# mother_card_03.net
KiCad netlist of a schematic drawn in EAGLE
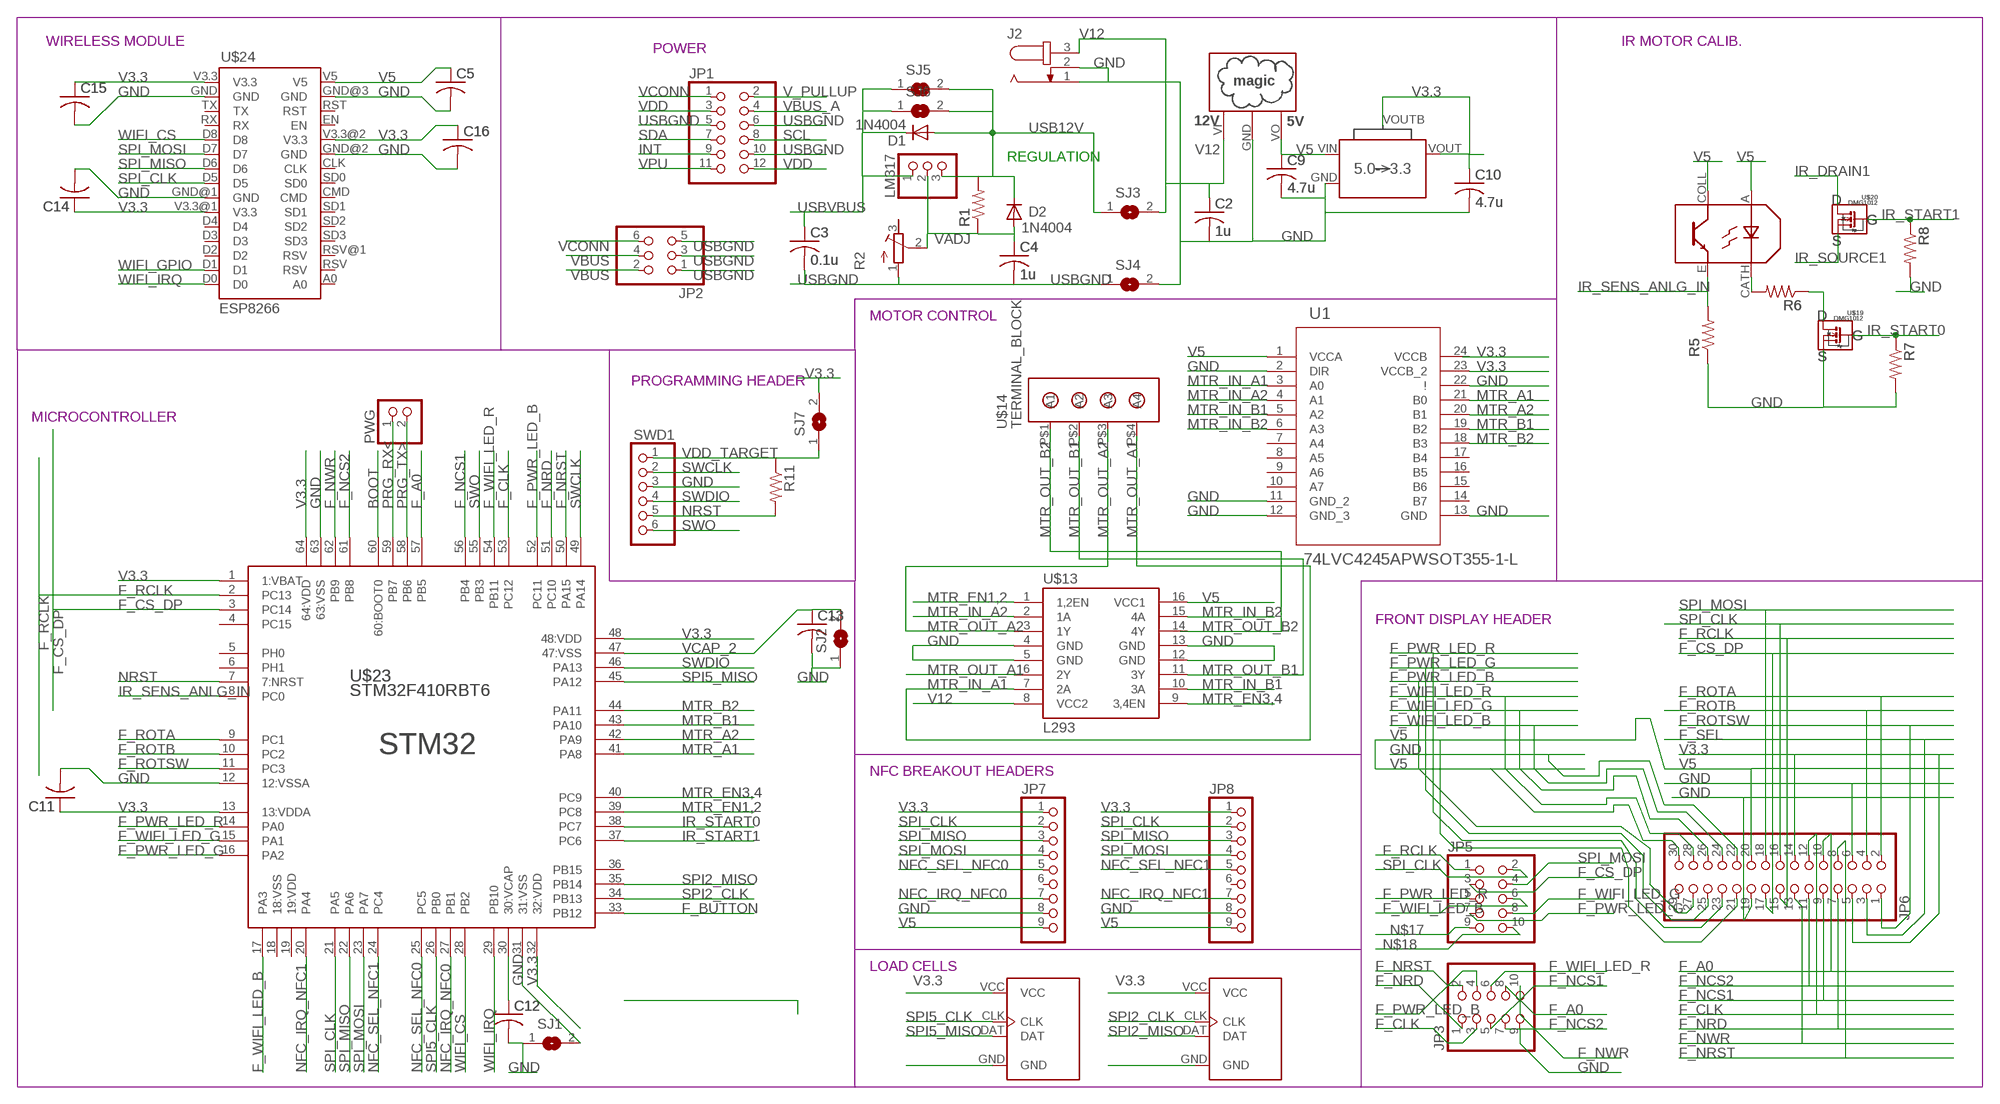
[diagram p0: schematic, sheet 1]

(export (version "E")
  (design (tool "Eeschema 10.0.6"))
  (components
    (comp (ref "C2")
      (value "1u")
      (footprint "eagle-import:C0805")
      (libsource (lib "eagle-import") (part "C-USC0805"))
    )
    (comp (ref "C3")
      (value "0.1u")
      (footprint "eagle-import:C0805")
      (libsource (lib "eagle-import") (part "C-USC0805"))
    )
    (comp (ref "C4")
      (value "1u")
      (footprint "eagle-import:C0805")
      (libsource (lib "eagle-import") (part "C-USC0805"))
    )
    (comp (ref "C5")
      (value "C-USC0805")
      (footprint "eagle-import:C0805")
      (libsource (lib "eagle-import") (part "C-USC0805"))
    )
    (comp (ref "C9")
      (value "4.7u")
      (footprint "eagle-import:C0805")
      (libsource (lib "eagle-import") (part "C-USC0805"))
    )
    (comp (ref "C10")
      (value "4.7u")
      (footprint "eagle-import:C0805")
      (libsource (lib "eagle-import") (part "C-USC0805"))
    )
    (comp (ref "C11")
      (value "C-USC0805")
      (footprint "eagle-import:C0805")
      (libsource (lib "eagle-import") (part "C-USC0805"))
    )
    (comp (ref "C12")
      (value "C-USC0805")
      (footprint "eagle-import:C0805")
      (libsource (lib "eagle-import") (part "C-USC0805"))
    )
    (comp (ref "C13")
      (value "C-USC0805")
      (footprint "eagle-import:C0805")
      (libsource (lib "eagle-import") (part "C-USC0805"))
    )
    (comp (ref "C14")
      (value "C-USC0805")
      (footprint "eagle-import:C0805")
      (libsource (lib "eagle-import") (part "C-USC0805"))
    )
    (comp (ref "C15")
      (value "C-USC0805")
      (footprint "eagle-import:C0805")
      (libsource (lib "eagle-import") (part "C-USC0805"))
    )
    (comp (ref "C16")
      (value "C-USC0805")
      (footprint "eagle-import:C0805")
      (libsource (lib "eagle-import") (part "C-USC0805"))
    )
    (comp (ref "D1")
      (value "1N4004")
      (footprint "eagle-import:DO41-10")
      (libsource (lib "eagle-import") (part "1N4004"))
    )
    (comp (ref "D2")
      (value "1N4004")
      (footprint "eagle-import:DO41-10")
      (libsource (lib "eagle-import") (part "1N4004"))
    )
    (comp (ref "J2")
      (value "JACK-PLUG0")
      (footprint "eagle-import:SPC4077")
      (libsource (lib "eagle-import") (part "JACK-PLUG0"))
    )
    (comp (ref "JP1")
      (value "PINHD-2X6")
      (footprint "eagle-import:2X06")
      (libsource (lib "eagle-import") (part "PINHD-2X6"))
    )
    (comp (ref "JP2")
      (value "PINHD-2X3")
      (footprint "eagle-import:2X03")
      (libsource (lib "eagle-import") (part "PINHD-2X3"))
    )
    (comp (ref "JP3")
      (value "PINHD-2X5")
      (footprint "eagle-import:2X05")
      (libsource (lib "eagle-import") (part "PINHD-2X5"))
    )
    (comp (ref "JP5")
      (value "PINHD-2X5")
      (footprint "eagle-import:2X05")
      (libsource (lib "eagle-import") (part "PINHD-2X5"))
    )
    (comp (ref "JP6")
      (value "PINHD-2X15/SOCK")
      (footprint "eagle-import:2X15_SOCK")
      (libsource (lib "eagle-import") (part "PINHD-2X15/SOCK"))
    )
    (comp (ref "JP7")
      (value "PINHD-1X9/90")
      (footprint "eagle-import:1X09_90")
      (libsource (lib "eagle-import") (part "PINHD-1X9/90"))
    )
    (comp (ref "JP8")
      (value "PINHD-1X9/90")
      (footprint "eagle-import:1X09_90")
      (libsource (lib "eagle-import") (part "PINHD-1X9/90"))
    )
    (comp (ref "LM317")
      (value "PINHD-1X3")
      (footprint "eagle-import:1X03")
      (libsource (lib "eagle-import") (part "PINHD-1X3"))
    )
    (comp (ref "PWG")
      (value "PINHD-1X2")
      (footprint "eagle-import:1X02")
      (libsource (lib "eagle-import") (part "PINHD-1X2"))
    )
    (comp (ref "R1")
      (value "R-US_R0805")
      (footprint "eagle-import:R0805")
      (libsource (lib "eagle-import") (part "seniorDesign_R-US_R0805"))
    )
    (comp (ref "R2")
      (value "R-TRIMM64W")
      (footprint "eagle-import:RTRIM64W")
      (libsource (lib "eagle-import") (part "R-TRIMM64W"))
    )
    (comp (ref "R5")
      (value "R-US_R0805")
      (footprint "eagle-import:R0805")
      (libsource (lib "eagle-import") (part "seniorDesign_R-US_R0805"))
    )
    (comp (ref "R6")
      (value "R-US_R0805")
      (footprint "eagle-import:R0805")
      (libsource (lib "eagle-import") (part "seniorDesign_R-US_R0805"))
    )
    (comp (ref "R7")
      (value "R-US_R0805")
      (footprint "eagle-import:R0805")
      (libsource (lib "eagle-import") (part "seniorDesign_R-US_R0805"))
    )
    (comp (ref "R8")
      (value "R-US_R0805")
      (footprint "eagle-import:R0805")
      (libsource (lib "eagle-import") (part "seniorDesign_R-US_R0805"))
    )
    (comp (ref "R11")
      (value "R-US_R0805")
      (footprint "eagle-import:R0805")
      (libsource (lib "eagle-import") (part "R-US_R0805"))
    )
    (comp (ref "SJ1") (value "SJ") (footprint "eagle-import:SJ") (libsource (lib "eagle-import") (part "SJ")))
    (comp (ref "SJ2") (value "SJ") (footprint "eagle-import:SJ") (libsource (lib "eagle-import") (part "SJ")))
    (comp (ref "SJ3") (value "SJ") (footprint "eagle-import:SJ") (libsource (lib "eagle-import") (part "SJ")))
    (comp (ref "SJ4") (value "SJ") (footprint "eagle-import:SJ") (libsource (lib "eagle-import") (part "SJ")))
    (comp (ref "SJ5") (value "SJ") (footprint "eagle-import:SJ") (libsource (lib "eagle-import") (part "SJ")))
    (comp (ref "SJ6") (value "SJ") (footprint "eagle-import:SJ") (libsource (lib "eagle-import") (part "SJ")))
    (comp (ref "SJ7") (value "SJ") (footprint "eagle-import:SJ") (libsource (lib "eagle-import") (part "SJ")))
    (comp (ref "SWD1")
      (value "PINHD-1X6")
      (footprint "eagle-import:1X06")
      (libsource (lib "eagle-import") (part "PINHD-1X6"))
    )
    (comp (ref "U$13")
      (value "L293")
      (footprint "eagle-import:DIL16")
      (libsource (lib "eagle-import") (part "L293"))
    )
    (comp (ref "U$14")
      (value "TERMINAL_BLOCK")
      (footprint "eagle-import:1X4_BLOCK")
      (libsource (lib "eagle-import") (part "TERMINAL_BLOCK"))
    )
    (comp (ref "U$15")
      (value "AP2114H")
      (footprint "eagle-import:AP2114H")
      (libsource (lib "eagle-import") (part "AP2114H"))
    )
    (comp (ref "U$16")
      (value "OKI-78SR-W36")
      (footprint "eagle-import:SIP3")
      (libsource (lib "eagle-import") (part "OKI-78SR-W36"))
    )
    (comp (ref "U$18")
      (value "TCRT5000")
      (footprint "eagle-import:TCRT5000")
      (libsource (lib "eagle-import") (part "TCRT5000"))
    )
    (comp (ref "U$19")
      (value "DMG1012")
      (footprint "eagle-import:SOT323")
      (libsource (lib "eagle-import") (part "DMG1012"))
    )
    (comp (ref "U$20")
      (value "DMG1012")
      (footprint "eagle-import:SOT323")
      (libsource (lib "eagle-import") (part "DMG1012"))
    )
    (comp (ref "U$21")
      (value "HX711")
      (footprint "eagle-import:HX711")
      (libsource (lib "eagle-import") (part "HX711"))
    )
    (comp (ref "U$22")
      (value "HX711")
      (footprint "eagle-import:HX711")
      (libsource (lib "eagle-import") (part "HX711"))
    )
    (comp (ref "U$23")
      (value "STM32F410RBT6")
      (footprint "eagle-import:QFP50P1200X1200X160-64N")
      (libsource (lib "eagle-import") (part "STM32F410RBT6"))
    )
    (comp (ref "U$24")
      (value "ESP8266")
      (footprint "eagle-import:ESP8266")
      (libsource (lib "eagle-import") (part "ESP8266"))
    )
    (comp (ref "U1")
      (value "74LVC4245APWSOT355-1-L")
      (footprint "eagle-import:SOT355-1-L")
      (fields (field (name "MANUFACTURER_PART_NUMBER") "74LVC4245APW"))
      (libsource (lib "eagle-import") (part "74LVC4245APWSOT355-1-L"))
    )
  )
  (nets
    (net (code "1") (name "/BOOT") (class "Default")
      (node (ref "U$23") (pin "60") (pinfunction "60:BOOT0_60") (pintype "bidirectional"))
    )
    (net (code "2") (name "/F_A0") (class "Default")
      (node (ref "JP3") (pin "8") (pinfunction "8_8") (pintype "passive"))
      (node (ref "JP6") (pin "10") (pinfunction "10_10") (pintype "passive"))
      (node (ref "U$23") (pin "57") (pinfunction "PB5_57") (pintype "bidirectional"))
    )
    (net (code "3") (name "/F_BUTTON") (class "Default")
      (node (ref "U$23") (pin "33") (pinfunction "PB12_33") (pintype "bidirectional"))
    )
    (net (code "4") (name "/F_CLK") (class "Default")
      (node (ref "JP3") (pin "3") (pinfunction "3_3") (pintype "passive"))
      (node (ref "JP6") (pin "12") (pinfunction "12_12") (pintype "passive"))
      (node (ref "U$23") (pin "53") (pinfunction "PC12_53") (pintype "bidirectional"))
    )
    (net (code "5") (name "/F_CS_DP") (class "Default")
      (node (ref "JP5") (pin "3") (pinfunction "3_3") (pintype "passive"))
      (node (ref "JP6") (pin "17") (pinfunction "17_17") (pintype "passive"))
      (node (ref "U$23") (pin "3") (pinfunction "PC14_3") (pintype "bidirectional"))
    )
    (net (code "6") (name "/F_NCS1") (class "Default")
      (node (ref "JP3") (pin "5") (pinfunction "5_5") (pintype "passive"))
      (node (ref "JP6") (pin "9") (pinfunction "9_9") (pintype "passive"))
      (node (ref "U$23") (pin "56") (pinfunction "PB4_56") (pintype "bidirectional"))
    )
    (net (code "7") (name "/F_NCS2") (class "Default")
      (node (ref "JP3") (pin "7") (pinfunction "7_7") (pintype "passive"))
      (node (ref "JP6") (pin "11") (pinfunction "11_11") (pintype "passive"))
      (node (ref "U$23") (pin "61") (pinfunction "PB8_61") (pintype "bidirectional"))
    )
    (net (code "8") (name "/F_NRD") (class "Default")
      (node (ref "JP3") (pin "1") (pinfunction "1_1") (pintype "passive"))
      (node (ref "JP6") (pin "7") (pinfunction "7_7") (pintype "passive"))
      (node (ref "U$23") (pin "51") (pinfunction "PC10_51") (pintype "bidirectional"))
    )
    (net (code "9") (name "/F_NRST") (class "Default")
      (node (ref "JP3") (pin "2") (pinfunction "2_2") (pintype "passive"))
      (node (ref "JP6") (pin "8") (pinfunction "8_8") (pintype "passive"))
      (node (ref "U$23") (pin "50") (pinfunction "PA15_50") (pintype "bidirectional"))
    )
    (net (code "10") (name "/F_NWR") (class "Default")
      (node (ref "JP3") (pin "10") (pinfunction "10_10") (pintype "passive"))
      (node (ref "JP6") (pin "13") (pinfunction "13_13") (pintype "passive"))
      (node (ref "U$23") (pin "62") (pinfunction "PB9_62") (pintype "bidirectional"))
    )
    (net (code "11") (name "/F_PWR_LED_B") (class "Default")
      (node (ref "JP3") (pin "4") (pinfunction "4_4") (pintype "passive"))
      (node (ref "JP6") (pin "27") (pinfunction "27_27") (pintype "passive"))
      (node (ref "U$23") (pin "52") (pinfunction "PC11_52") (pintype "bidirectional"))
    )
    (net (code "12") (name "/F_PWR_LED_G") (class "Default")
      (node (ref "JP5") (pin "7") (pinfunction "7_7") (pintype "passive"))
      (node (ref "JP6") (pin "25") (pinfunction "25_25") (pintype "passive"))
      (node (ref "U$23") (pin "16") (pinfunction "PA2_16") (pintype "bidirectional"))
    )
    (net (code "13") (name "/F_PWR_LED_R") (class "Default")
      (node (ref "JP5") (pin "5") (pinfunction "5_5") (pintype "passive"))
      (node (ref "JP6") (pin "23") (pinfunction "23_23") (pintype "passive"))
      (node (ref "U$23") (pin "14") (pinfunction "PA0_14") (pintype "bidirectional"))
    )
    (net (code "14") (name "/F_RCLK") (class "Default")
      (node (ref "JP5") (pin "1") (pinfunction "1_1") (pintype "passive"))
      (node (ref "JP6") (pin "15") (pinfunction "15_15") (pintype "passive"))
      (node (ref "U$23") (pin "2") (pinfunction "PC13_2") (pintype "bidirectional"))
    )
    (net (code "15") (name "/F_ROTA") (class "Default")
      (node (ref "JP6") (pin "2") (pinfunction "2_2") (pintype "passive"))
      (node (ref "U$23") (pin "9") (pinfunction "PC1_9") (pintype "bidirectional"))
    )
    (net (code "16") (name "/F_ROTB") (class "Default")
      (node (ref "JP6") (pin "4") (pinfunction "4_4") (pintype "passive"))
      (node (ref "U$23") (pin "10") (pinfunction "PC2_10") (pintype "bidirectional"))
    )
    (net (code "17") (name "/F_ROTSW") (class "Default")
      (node (ref "JP6") (pin "1") (pinfunction "1_1") (pintype "passive"))
      (node (ref "U$23") (pin "11") (pinfunction "PC3_11") (pintype "bidirectional"))
    )
    (net (code "18") (name "/F_SEL") (class "Default")
      (node (ref "JP6") (pin "3") (pinfunction "3_3") (pintype "passive"))
    )
    (net (code "19") (name "/F_WIFI_LED_B") (class "Default")
      (node (ref "JP5") (pin "6") (pinfunction "6_6") (pintype "passive"))
      (node (ref "JP6") (pin "24") (pinfunction "24_24") (pintype "passive"))
      (node (ref "U$23") (pin "17") (pinfunction "PA3_17") (pintype "bidirectional"))
    )
    (net (code "20") (name "/F_WIFI_LED_G") (class "Default")
      (node (ref "JP5") (pin "8") (pinfunction "8_8") (pintype "passive"))
      (node (ref "JP6") (pin "26") (pinfunction "26_26") (pintype "passive"))
      (node (ref "U$23") (pin "15") (pinfunction "PA1_15") (pintype "bidirectional"))
    )
    (net (code "21") (name "/F_WIFI_LED_R") (class "Default")
      (node (ref "JP3") (pin "6") (pinfunction "6_6") (pintype "passive"))
      (node (ref "JP6") (pin "28") (pinfunction "28_28") (pintype "passive"))
      (node (ref "U$23") (pin "54") (pinfunction "PB11_54") (pintype "bidirectional"))
    )
    (net (code "22") (name "/GND") (class "Default")
      (node (ref "C10") (pin "2") (pinfunction "2_2") (pintype "passive"))
      (node (ref "C11") (pin "2") (pinfunction "2_2") (pintype "passive"))
      (node (ref "C12") (pin "2") (pinfunction "2_2") (pintype "passive"))
      (node (ref "C13") (pin "2") (pinfunction "2_2") (pintype "passive"))
      (node (ref "C14") (pin "2") (pinfunction "2_2") (pintype "passive"))
      (node (ref "C15") (pin "2") (pinfunction "2_2") (pintype "passive"))
      (node (ref "C16") (pin "2") (pinfunction "2_2") (pintype "passive"))
      (node (ref "C2") (pin "2") (pinfunction "2_2") (pintype "passive"))
      (node (ref "C5") (pin "2") (pinfunction "2_2") (pintype "passive"))
      (node (ref "C9") (pin "2") (pinfunction "2_2") (pintype "passive"))
      (node (ref "J2") (pin "1") (pinfunction "1_1") (pintype "passive"))
      (node (ref "J2") (pin "2") (pinfunction "2_2") (pintype "passive"))
      (node (ref "JP3") (pin "9") (pinfunction "9_9") (pintype "passive"))
      (node (ref "JP6") (pin "19") (pinfunction "19_19") (pintype "passive"))
      (node (ref "JP6") (pin "22") (pinfunction "22_22") (pintype "passive"))
      (node (ref "JP6") (pin "6") (pinfunction "6_6") (pintype "passive"))
      (node (ref "JP7") (pin "8") (pinfunction "8_8") (pintype "passive"))
      (node (ref "JP8") (pin "8") (pinfunction "8_8") (pintype "passive"))
      (node (ref "R5") (pin "1") (pinfunction "1_1") (pintype "passive"))
      (node (ref "R7") (pin "2") (pinfunction "2_2") (pintype "passive"))
      (node (ref "R8") (pin "2") (pinfunction "2_2") (pintype "passive"))
      (node (ref "SJ1") (pin "1") (pinfunction "1_1") (pintype "passive"))
      (node (ref "SJ1") (pin "2") (pinfunction "2_2") (pintype "passive"))
      (node (ref "SJ2") (pin "1") (pinfunction "1_1") (pintype "passive"))
      (node (ref "SJ4") (pin "2") (pinfunction "2_2") (pintype "passive"))
      (node (ref "SWD1") (pin "3") (pinfunction "3_3") (pintype "passive"))
      (node (ref "U$13") (pin "12") (pinfunction "GND_12") (pintype "bidirectional"))
      (node (ref "U$13") (pin "13") (pinfunction "GND_13") (pintype "bidirectional"))
      (node (ref "U$13") (pin "4") (pinfunction "GND_4") (pintype "bidirectional"))
      (node (ref "U$13") (pin "5") (pinfunction "GND_5") (pintype "bidirectional"))
      (node (ref "U$15") (pin "GND") (pinfunction "GND_GND") (pintype "power_in"))
      (node (ref "U$16") (pin "GND") (pinfunction "P$2_GND") (pintype "power_in"))
      (node (ref "U$19") (pin "S") (pinfunction "S_S") (pintype "bidirectional"))
      (node (ref "U$21") (pin "GND") (pinfunction "GND_GND") (pintype "power_in"))
      (node (ref "U$22") (pin "GND") (pinfunction "GND_GND") (pintype "power_in"))
      (node (ref "U$23") (pin "12") (pinfunction "12:VSSA_12") (pintype "bidirectional"))
      (node (ref "U$23") (pin "31") (pinfunction "31:VSS_31") (pintype "bidirectional"))
      (node (ref "U$23") (pin "63") (pinfunction "63:VSS_63") (pintype "bidirectional"))
      (node (ref "U$24") (pin "GND") (pinfunction "GND_GND") (pintype "bidirectional"))
      (node (ref "U$24") (pin "GND@1") (pinfunction "GND_GND@1") (pintype "bidirectional"))
      (node (ref "U$24") (pin "GND@2") (pinfunction "GND_GND@2") (pintype "bidirectional"))
      (node (ref "U$24") (pin "GND@3") (pinfunction "GND_GND@3") (pintype "bidirectional"))
      (node (ref "U1") (pin "11") (pinfunction "GND_2_11") (pintype "power_in"))
      (node (ref "U1") (pin "12") (pinfunction "GND_3_12") (pintype "power_in"))
      (node (ref "U1") (pin "13") (pinfunction "GND_13") (pintype "power_in"))
      (node (ref "U1") (pin "2") (pinfunction "DIR_2") (pintype "input"))
      (node (ref "U1") (pin "22") (pinfunction "~_22") (pintype "input"))
    )
    (net (code "23") (name "/INT") (class "Default")
      (node (ref "JP1") (pin "9") (pinfunction "9_9") (pintype "passive"))
    )
    (net (code "24") (name "/IR_DRAIN1") (class "Default")
      (node (ref "U$20") (pin "D") (pinfunction "D_D") (pintype "bidirectional"))
    )
    (net (code "25") (name "/IR_SENS_ANLG_IN") (class "Default")
      (node (ref "R5") (pin "2") (pinfunction "2_2") (pintype "passive"))
      (node (ref "U$18") (pin "E") (pinfunction "E_E") (pintype "bidirectional"))
      (node (ref "U$23") (pin "8") (pinfunction "PC0_8") (pintype "bidirectional"))
    )
    (net (code "26") (name "/IR_SOURCE1") (class "Default")
      (node (ref "U$20") (pin "S") (pinfunction "S_S") (pintype "bidirectional"))
    )
    (net (code "27") (name "/IR_START0") (class "Default")
      (node (ref "R7") (pin "1") (pinfunction "1_1") (pintype "passive"))
      (node (ref "U$19") (pin "G") (pinfunction "G_G") (pintype "bidirectional"))
      (node (ref "U$23") (pin "38") (pinfunction "PC7_38") (pintype "bidirectional"))
    )
    (net (code "28") (name "/IR_START1") (class "Default")
      (node (ref "R8") (pin "1") (pinfunction "1_1") (pintype "passive"))
      (node (ref "U$20") (pin "G") (pinfunction "G_G") (pintype "bidirectional"))
      (node (ref "U$23") (pin "37") (pinfunction "PC6_37") (pintype "bidirectional"))
    )
    (net (code "29") (name "/MTR_A1") (class "Default")
      (node (ref "U$23") (pin "41") (pinfunction "PA8_41") (pintype "bidirectional"))
      (node (ref "U1") (pin "21") (pinfunction "B0_21") (pintype "bidirectional"))
    )
    (net (code "30") (name "/MTR_A2") (class "Default")
      (node (ref "U$23") (pin "42") (pinfunction "PA9_42") (pintype "bidirectional"))
      (node (ref "U1") (pin "20") (pinfunction "B1_20") (pintype "bidirectional"))
    )
    (net (code "31") (name "/MTR_B1") (class "Default")
      (node (ref "U$23") (pin "43") (pinfunction "PA10_43") (pintype "bidirectional"))
      (node (ref "U1") (pin "19") (pinfunction "B2_19") (pintype "bidirectional"))
    )
    (net (code "32") (name "/MTR_B2") (class "Default")
      (node (ref "U$23") (pin "44") (pinfunction "PA11_44") (pintype "bidirectional"))
      (node (ref "U1") (pin "18") (pinfunction "B3_18") (pintype "bidirectional"))
    )
    (net (code "33") (name "/MTR_EN1,2") (class "Default")
      (node (ref "U$13") (pin "1") (pinfunction "1,2EN_1") (pintype "bidirectional"))
      (node (ref "U$23") (pin "39") (pinfunction "PC8_39") (pintype "bidirectional"))
    )
    (net (code "34") (name "/MTR_EN3,4") (class "Default")
      (node (ref "U$13") (pin "9") (pinfunction "3,4EN_9") (pintype "bidirectional"))
      (node (ref "U$23") (pin "40") (pinfunction "PC9_40") (pintype "bidirectional"))
    )
    (net (code "35") (name "/MTR_IN_A1") (class "Default")
      (node (ref "U$13") (pin "7") (pinfunction "2A_7") (pintype "bidirectional"))
      (node (ref "U$14") (pin "P$4") (pinfunction "A4_P$4") (pintype "bidirectional"))
      (node (ref "U1") (pin "3") (pinfunction "A0_3") (pintype "bidirectional"))
    )
    (net (code "36") (name "/MTR_IN_A2") (class "Default")
      (node (ref "U$13") (pin "2") (pinfunction "1A_2") (pintype "bidirectional"))
      (node (ref "U1") (pin "4") (pinfunction "A1_4") (pintype "bidirectional"))
    )
    (net (code "37") (name "/MTR_IN_B1") (class "Default")
      (node (ref "U$13") (pin "10") (pinfunction "3A_10") (pintype "bidirectional"))
      (node (ref "U1") (pin "5") (pinfunction "A2_5") (pintype "bidirectional"))
    )
    (net (code "38") (name "/MTR_IN_B2") (class "Default")
      (node (ref "U$13") (pin "15") (pinfunction "4A_15") (pintype "bidirectional"))
      (node (ref "U1") (pin "6") (pinfunction "A3_6") (pintype "bidirectional"))
    )
    (net (code "39") (name "/MTR_OUT_A1") (class "Default")
      (node (ref "U$13") (pin "6") (pinfunction "2Y_6") (pintype "bidirectional"))
    )
    (net (code "40") (name "/MTR_OUT_A2") (class "Default")
      (node (ref "U$13") (pin "3") (pinfunction "1Y_3") (pintype "bidirectional"))
      (node (ref "U$14") (pin "P$3") (pinfunction "A3_P$3") (pintype "bidirectional"))
    )
    (net (code "41") (name "/MTR_OUT_B1") (class "Default")
      (node (ref "U$13") (pin "11") (pinfunction "3Y_11") (pintype "bidirectional"))
      (node (ref "U$14") (pin "P$2") (pinfunction "A2_P$2") (pintype "bidirectional"))
    )
    (net (code "42") (name "/MTR_OUT_B2") (class "Default")
      (node (ref "U$13") (pin "14") (pinfunction "4Y_14") (pintype "bidirectional"))
      (node (ref "U$14") (pin "P$1") (pinfunction "A1_P$1") (pintype "bidirectional"))
    )
    (net (code "43") (name "/N$17") (class "Default")
      (node (ref "JP5") (pin "9") (pinfunction "9_9") (pintype "passive"))
    )
    (net (code "44") (name "/N$18") (class "Default")
      (node (ref "JP5") (pin "10") (pinfunction "10_10") (pintype "passive"))
    )
    (net (code "45") (name "/NFC_IRQ_NFC0") (class "Default")
      (node (ref "JP7") (pin "7") (pinfunction "7_7") (pintype "passive"))
      (node (ref "U$23") (pin "27") (pinfunction "PB1_27") (pintype "bidirectional"))
    )
    (net (code "46") (name "/NFC_IRQ_NFC1") (class "Default")
      (node (ref "JP8") (pin "7") (pinfunction "7_7") (pintype "passive"))
      (node (ref "U$23") (pin "20") (pinfunction "PA4_20") (pintype "bidirectional"))
    )
    (net (code "47") (name "/NFC_SEL_NFC0") (class "Default")
      (node (ref "JP7") (pin "5") (pinfunction "5_5") (pintype "passive"))
      (node (ref "U$23") (pin "25") (pinfunction "PC5_25") (pintype "bidirectional"))
    )
    (net (code "48") (name "/NFC_SEL_NFC1") (class "Default")
      (node (ref "JP8") (pin "5") (pinfunction "5_5") (pintype "passive"))
      (node (ref "U$23") (pin "24") (pinfunction "PC4_24") (pintype "bidirectional"))
    )
    (net (code "49") (name "/NRST") (class "Default")
      (node (ref "R11") (pin "2") (pinfunction "2_2") (pintype "passive"))
      (node (ref "SWD1") (pin "5") (pinfunction "5_5") (pintype "passive"))
      (node (ref "U$23") (pin "7") (pinfunction "7:NRST_7") (pintype "bidirectional"))
    )
    (net (code "50") (name "/PRG_RX<") (class "Default")
      (node (ref "PWG") (pin "1") (pinfunction "1_1") (pintype "passive"))
      (node (ref "U$23") (pin "59") (pinfunction "PB7_59") (pintype "bidirectional"))
    )
    (net (code "51") (name "/PRG_TX>") (class "Default")
      (node (ref "PWG") (pin "2") (pinfunction "2_2") (pintype "passive"))
      (node (ref "U$23") (pin "58") (pinfunction "PB6_58") (pintype "bidirectional"))
    )
    (net (code "52") (name "/SCL") (class "Default")
      (node (ref "JP1") (pin "8") (pinfunction "8_8") (pintype "passive"))
    )
    (net (code "53") (name "/SDA") (class "Default")
      (node (ref "JP1") (pin "7") (pinfunction "7_7") (pintype "passive"))
    )
    (net (code "54") (name "/SPI2_CLK") (class "Default")
      (node (ref "U$22") (pin "CLK") (pinfunction "CLK_CLK") (pintype "bidirectional"))
      (node (ref "U$23") (pin "34") (pinfunction "PB13_34") (pintype "bidirectional"))
    )
    (net (code "55") (name "/SPI2_MISO") (class "Default")
      (node (ref "U$22") (pin "DAT") (pinfunction "DAT_DAT") (pintype "bidirectional"))
      (node (ref "U$23") (pin "35") (pinfunction "PB14_35") (pintype "bidirectional"))
    )
    (net (code "56") (name "/SPI5_CLK") (class "Default")
      (node (ref "U$21") (pin "CLK") (pinfunction "CLK_CLK") (pintype "bidirectional"))
      (node (ref "U$23") (pin "26") (pinfunction "PB0_26") (pintype "bidirectional"))
    )
    (net (code "57") (name "/SPI5_MISO") (class "Default")
      (node (ref "U$21") (pin "DAT") (pinfunction "DAT_DAT") (pintype "bidirectional"))
      (node (ref "U$23") (pin "45") (pinfunction "PA12_45") (pintype "bidirectional"))
    )
    (net (code "58") (name "/SPI_CLK") (class "Default")
      (node (ref "JP5") (pin "2") (pinfunction "2_2") (pintype "passive"))
      (node (ref "JP6") (pin "16") (pinfunction "16_16") (pintype "passive"))
      (node (ref "JP7") (pin "2") (pinfunction "2_2") (pintype "passive"))
      (node (ref "JP8") (pin "2") (pinfunction "2_2") (pintype "passive"))
      (node (ref "U$23") (pin "21") (pinfunction "PA5_21") (pintype "bidirectional"))
      (node (ref "U$24") (pin "D5") (pinfunction "D5_D5") (pintype "bidirectional"))
    )
    (net (code "59") (name "/SPI_MISO") (class "Default")
      (node (ref "JP7") (pin "3") (pinfunction "3_3") (pintype "passive"))
      (node (ref "JP8") (pin "3") (pinfunction "3_3") (pintype "passive"))
      (node (ref "U$23") (pin "22") (pinfunction "PA6_22") (pintype "bidirectional"))
      (node (ref "U$24") (pin "D6") (pinfunction "D6_D6") (pintype "bidirectional"))
    )
    (net (code "60") (name "/SPI_MOSI") (class "Default")
      (node (ref "JP5") (pin "4") (pinfunction "4_4") (pintype "passive"))
      (node (ref "JP6") (pin "18") (pinfunction "18_18") (pintype "passive"))
      (node (ref "JP7") (pin "4") (pinfunction "4_4") (pintype "passive"))
      (node (ref "JP8") (pin "4") (pinfunction "4_4") (pintype "passive"))
      (node (ref "U$23") (pin "23") (pinfunction "PA7_23") (pintype "bidirectional"))
      (node (ref "U$24") (pin "D7") (pinfunction "D7_D7") (pintype "bidirectional"))
    )
    (net (code "61") (name "/SWCLK") (class "Default")
      (node (ref "SWD1") (pin "2") (pinfunction "2_2") (pintype "passive"))
      (node (ref "U$23") (pin "49") (pinfunction "PA14_49") (pintype "bidirectional"))
    )
    (net (code "62") (name "/SWDIO") (class "Default")
      (node (ref "SWD1") (pin "4") (pinfunction "4_4") (pintype "passive"))
      (node (ref "U$23") (pin "46") (pinfunction "PA13_46") (pintype "bidirectional"))
    )
    (net (code "63") (name "/SWO") (class "Default")
      (node (ref "SWD1") (pin "6") (pinfunction "6_6") (pintype "passive"))
      (node (ref "U$23") (pin "55") (pinfunction "PB3_55") (pintype "bidirectional"))
    )
    (net (code "64") (name "/USB12V") (class "Default")
      (node (ref "D1") (pin "A") (pinfunction "A_A") (pintype "passive"))
      (node (ref "D2") (pin "C") (pinfunction "C_C") (pintype "passive"))
      (node (ref "LM317") (pin "3") (pinfunction "3_3") (pintype "passive"))
      (node (ref "R1") (pin "2") (pinfunction "2_2") (pintype "passive"))
      (node (ref "SJ3") (pin "1") (pinfunction "1_1") (pintype "passive"))
      (node (ref "SJ5") (pin "2") (pinfunction "2_2") (pintype "passive"))
      (node (ref "SJ6") (pin "2") (pinfunction "2_2") (pintype "passive"))
    )
    (net (code "65") (name "/USBGND") (class "Default")
      (node (ref "C3") (pin "2") (pinfunction "2_2") (pintype "passive"))
      (node (ref "C4") (pin "2") (pinfunction "2_2") (pintype "passive"))
      (node (ref "JP1") (pin "10") (pinfunction "10_10") (pintype "passive"))
      (node (ref "JP1") (pin "5") (pinfunction "5_5") (pintype "passive"))
      (node (ref "JP1") (pin "6") (pinfunction "6_6") (pintype "passive"))
      (node (ref "JP2") (pin "1") (pinfunction "1_1") (pintype "passive"))
      (node (ref "JP2") (pin "3") (pinfunction "3_3") (pintype "passive"))
      (node (ref "JP2") (pin "5") (pinfunction "5_5") (pintype "passive"))
      (node (ref "R2") (pin "1") (pinfunction "A_1") (pintype "passive"))
      (node (ref "SJ4") (pin "1") (pinfunction "1_1") (pintype "passive"))
    )
    (net (code "66") (name "/USBVBUS") (class "Default")
      (node (ref "C3") (pin "1") (pinfunction "1_1") (pintype "passive"))
      (node (ref "D1") (pin "C") (pinfunction "C_C") (pintype "passive"))
      (node (ref "LM317") (pin "1") (pinfunction "1_1") (pintype "passive"))
      (node (ref "SJ5") (pin "1") (pinfunction "1_1") (pintype "passive"))
      (node (ref "SJ6") (pin "1") (pinfunction "1_1") (pintype "passive"))
    )
    (net (code "67") (name "/V3.3") (class "Default")
      (node (ref "C10") (pin "1") (pinfunction "1_1") (pintype "passive"))
      (node (ref "C11") (pin "1") (pinfunction "1_1") (pintype "passive"))
      (node (ref "C14") (pin "1") (pinfunction "1_1") (pintype "passive"))
      (node (ref "C15") (pin "1") (pinfunction "1_1") (pintype "passive"))
      (node (ref "C16") (pin "1") (pinfunction "1_1") (pintype "passive"))
      (node (ref "JP6") (pin "14") (pinfunction "14_14") (pintype "passive"))
      (node (ref "JP6") (pin "5") (pinfunction "5_5") (pintype "passive"))
      (node (ref "JP7") (pin "1") (pinfunction "1_1") (pintype "passive"))
      (node (ref "JP8") (pin "1") (pinfunction "1_1") (pintype "passive"))
      (node (ref "SJ7") (pin "2") (pinfunction "2_2") (pintype "passive"))
      (node (ref "U$15") (pin "VOUT") (pinfunction "VO_VOUT") (pintype "output"))
      (node (ref "U$15") (pin "VOUTB") (pinfunction "BODY_VOUTB") (pintype "open_collector"))
      (node (ref "U$21") (pin "VCC") (pinfunction "VCC_VCC") (pintype "power_in"))
      (node (ref "U$22") (pin "VCC") (pinfunction "VCC_VCC") (pintype "power_in"))
      (node (ref "U$23") (pin "1") (pinfunction "1:VBAT_1") (pintype "bidirectional"))
      (node (ref "U$23") (pin "13") (pinfunction "13:VDDA_13") (pintype "bidirectional"))
      (node (ref "U$23") (pin "32") (pinfunction "32:VDD_32") (pintype "bidirectional"))
      (node (ref "U$23") (pin "48") (pinfunction "48:VDD_48") (pintype "bidirectional"))
      (node (ref "U$23") (pin "64") (pinfunction "64:VDD_64") (pintype "bidirectional"))
      (node (ref "U$24") (pin "V3.3") (pinfunction "V3.3_V3.3") (pintype "bidirectional"))
      (node (ref "U$24") (pin "V3.3@1") (pinfunction "V3.3_V3.3@1") (pintype "bidirectional"))
      (node (ref "U$24") (pin "V3.3@2") (pinfunction "V3.3_V3.3@2") (pintype "bidirectional"))
      (node (ref "U1") (pin "23") (pinfunction "VCCB_2_23") (pintype "power_in"))
      (node (ref "U1") (pin "24") (pinfunction "VCCB_24") (pintype "power_in"))
    )
    (net (code "68") (name "/V5") (class "Default")
      (node (ref "C5") (pin "1") (pinfunction "1_1") (pintype "passive"))
      (node (ref "C9") (pin "1") (pinfunction "1_1") (pintype "passive"))
      (node (ref "JP6") (pin "20") (pinfunction "20_20") (pintype "passive"))
      (node (ref "JP6") (pin "21") (pinfunction "21_21") (pintype "passive"))
      (node (ref "JP6") (pin "30") (pinfunction "30_30") (pintype "passive"))
      (node (ref "JP7") (pin "9") (pinfunction "9_9") (pintype "passive"))
      (node (ref "JP8") (pin "9") (pinfunction "9_9") (pintype "passive"))
      (node (ref "U$13") (pin "16") (pinfunction "VCC1_16") (pintype "bidirectional"))
      (node (ref "U$15") (pin "VIN") (pinfunction "VI_VIN") (pintype "input"))
      (node (ref "U$16") (pin "VO") (pinfunction "P$3_VO") (pintype "output"))
      (node (ref "U$18") (pin "A") (pinfunction "A_A") (pintype "bidirectional"))
      (node (ref "U$18") (pin "COLL") (pinfunction "COLL_COLL") (pintype "bidirectional"))
      (node (ref "U$24") (pin "V5") (pinfunction "V5_V5") (pintype "bidirectional"))
      (node (ref "U1") (pin "1") (pinfunction "VCCA_1") (pintype "power_in"))
    )
    (net (code "69") (name "/V12") (class "Default")
      (node (ref "C2") (pin "1") (pinfunction "1_1") (pintype "passive"))
      (node (ref "J2") (pin "3") (pinfunction "3_3") (pintype "passive"))
      (node (ref "SJ3") (pin "2") (pinfunction "2_2") (pintype "passive"))
      (node (ref "U$13") (pin "8") (pinfunction "VCC2_8") (pintype "bidirectional"))
      (node (ref "U$16") (pin "VI") (pinfunction "P$1_VI") (pintype "input"))
    )
    (net (code "70") (name "/VADJ") (class "Default")
      (node (ref "C4") (pin "1") (pinfunction "1_1") (pintype "passive"))
      (node (ref "D2") (pin "A") (pinfunction "A_A") (pintype "passive"))
      (node (ref "LM317") (pin "2") (pinfunction "2_2") (pintype "passive"))
      (node (ref "R1") (pin "1") (pinfunction "1_1") (pintype "passive"))
      (node (ref "R2") (pin "2") (pinfunction "S_2") (pintype "passive"))
    )
    (net (code "71") (name "/VBUS") (class "Default")
      (node (ref "JP2") (pin "2") (pinfunction "2_2") (pintype "passive"))
      (node (ref "JP2") (pin "4") (pinfunction "4_4") (pintype "passive"))
    )
    (net (code "72") (name "/VBUS_A") (class "Default")
      (node (ref "JP1") (pin "4") (pinfunction "4_4") (pintype "passive"))
    )
    (net (code "73") (name "/VCAP_2") (class "Default")
      (node (ref "C13") (pin "1") (pinfunction "1_1") (pintype "passive"))
      (node (ref "SJ2") (pin "2") (pinfunction "2_2") (pintype "passive"))
      (node (ref "U$23") (pin "47") (pinfunction "47:VSS_47") (pintype "bidirectional"))
    )
    (net (code "74") (name "/VCONN") (class "Default")
      (node (ref "JP1") (pin "1") (pinfunction "1_1") (pintype "passive"))
      (node (ref "JP2") (pin "6") (pinfunction "6_6") (pintype "passive"))
    )
    (net (code "75") (name "/VDD") (class "Default")
      (node (ref "JP1") (pin "12") (pinfunction "12_12") (pintype "passive"))
      (node (ref "JP1") (pin "3") (pinfunction "3_3") (pintype "passive"))
    )
    (net (code "76") (name "/VDD_TARGET") (class "Default")
      (node (ref "R11") (pin "1") (pinfunction "1_1") (pintype "passive"))
      (node (ref "SJ7") (pin "1") (pinfunction "1_1") (pintype "passive"))
      (node (ref "SWD1") (pin "1") (pinfunction "1_1") (pintype "passive"))
    )
    (net (code "77") (name "/VPU") (class "Default")
      (node (ref "JP1") (pin "11") (pinfunction "11_11") (pintype "passive"))
    )
    (net (code "78") (name "/V_PULLUP") (class "Default")
      (node (ref "JP1") (pin "2") (pinfunction "2_2") (pintype "passive"))
    )
    (net (code "79") (name "/WIFI_CS") (class "Default")
      (node (ref "U$23") (pin "28") (pinfunction "PB2_28") (pintype "bidirectional"))
      (node (ref "U$24") (pin "D8") (pinfunction "D8_D8") (pintype "bidirectional"))
    )
    (net (code "80") (name "/WIFI_GPIO") (class "Default")
      (node (ref "U$24") (pin "D1") (pinfunction "D1_D1") (pintype "bidirectional"))
    )
    (net (code "81") (name "/WIFI_IRQ") (class "Default")
      (node (ref "U$23") (pin "29") (pinfunction "PB10_29") (pintype "bidirectional"))
      (node (ref "U$24") (pin "D0") (pinfunction "D0_D0") (pintype "bidirectional"))
    )
    (net (code "82") (name "Net-(R6-Pad1)") (class "Default")
      (node (ref "R6") (pin "1") (pinfunction "1_1") (pintype "passive"))
      (node (ref "U$19") (pin "D") (pinfunction "D_D") (pintype "bidirectional"))
    )
    (net (code "83") (name "Net-(R6-Pad2)") (class "Default")
      (node (ref "R6") (pin "2") (pinfunction "2_2") (pintype "passive"))
      (node (ref "U$18") (pin "CATH") (pinfunction "CATH_CATH") (pintype "bidirectional"))
    )
    (net (code "84") (name "Net-(U$23-30:VCAP)") (class "Default")
      (node (ref "C12") (pin "1") (pinfunction "1_1") (pintype "passive"))
      (node (ref "U$23") (pin "30") (pinfunction "30:VCAP_30") (pintype "bidirectional"))
    )
    (net (code "85") (name "unconnected-(JP6-Pad29)") (class "Default")
      (node (ref "JP6") (pin "29") (pinfunction "29_29") (pintype "passive"))
    )
    (net (code "86") (name "unconnected-(JP7-Pad6)") (class "Default")
      (node (ref "JP7") (pin "6") (pinfunction "6_6") (pintype "passive"))
    )
    (net (code "87") (name "unconnected-(JP8-Pad6)") (class "Default")
      (node (ref "JP8") (pin "6") (pinfunction "6_6") (pintype "passive"))
    )
    (net (code "88") (name "unconnected-(R2-E-Pad3)") (class "Default")
      (node (ref "R2") (pin "3") (pinfunction "E_3") (pintype "passive"))
    )
    (net (code "89") (name "unconnected-(U$23-18:VSS-Pad18)") (class "Default")
      (node (ref "U$23") (pin "18") (pinfunction "18:VSS_18") (pintype "bidirectional"))
    )
    (net (code "90") (name "unconnected-(U$23-19:VDD-Pad19)") (class "Default")
      (node (ref "U$23") (pin "19") (pinfunction "19:VDD_19") (pintype "bidirectional"))
    )
    (net (code "91") (name "unconnected-(U$23-PB15-Pad36)") (class "Default")
      (node (ref "U$23") (pin "36") (pinfunction "PB15_36") (pintype "bidirectional"))
    )
    (net (code "92") (name "unconnected-(U$23-PC15-Pad4)") (class "Default")
      (node (ref "U$23") (pin "4") (pinfunction "PC15_4") (pintype "bidirectional"))
    )
    (net (code "93") (name "unconnected-(U$23-PH0-Pad5)") (class "Default")
      (node (ref "U$23") (pin "5") (pinfunction "PH0_5") (pintype "bidirectional"))
    )
    (net (code "94") (name "unconnected-(U$23-PH1-Pad6)") (class "Default")
      (node (ref "U$23") (pin "6") (pinfunction "PH1_6") (pintype "bidirectional"))
    )
    (net (code "95") (name "unconnected-(U$24-PadA0)") (class "Default")
      (node (ref "U$24") (pin "A0") (pinfunction "A0_A0") (pintype "bidirectional"))
    )
    (net (code "96") (name "unconnected-(U$24-PadCLK)") (class "Default")
      (node (ref "U$24") (pin "CLK") (pinfunction "CLK_CLK") (pintype "bidirectional"))
    )
    (net (code "97") (name "unconnected-(U$24-PadCMD)") (class "Default")
      (node (ref "U$24") (pin "CMD") (pinfunction "CMD_CMD") (pintype "bidirectional"))
    )
    (net (code "98") (name "unconnected-(U$24-PadD2)") (class "Default")
      (node (ref "U$24") (pin "D2") (pinfunction "D2_D2") (pintype "bidirectional"))
    )
    (net (code "99") (name "unconnected-(U$24-PadD3)") (class "Default")
      (node (ref "U$24") (pin "D3") (pinfunction "D3_D3") (pintype "bidirectional"))
    )
    (net (code "100") (name "unconnected-(U$24-PadD4)") (class "Default")
      (node (ref "U$24") (pin "D4") (pinfunction "D4_D4") (pintype "bidirectional"))
    )
    (net (code "101") (name "unconnected-(U$24-PadEN)") (class "Default")
      (node (ref "U$24") (pin "EN") (pinfunction "EN_EN") (pintype "bidirectional"))
    )
    (net (code "102") (name "unconnected-(U$24-PadRST)") (class "Default")
      (node (ref "U$24") (pin "RST") (pinfunction "RST_RST") (pintype "bidirectional"))
    )
    (net (code "103") (name "unconnected-(U$24-PadRSV)") (class "Default")
      (node (ref "U$24") (pin "RSV") (pinfunction "RSV_RSV") (pintype "bidirectional"))
    )
    (net (code "104") (name "unconnected-(U$24-PadRX)") (class "Default")
      (node (ref "U$24") (pin "RX") (pinfunction "RX_RX") (pintype "bidirectional"))
    )
    (net (code "105") (name "unconnected-(U$24-PadSD0)") (class "Default")
      (node (ref "U$24") (pin "SD0") (pinfunction "SD0_SD0") (pintype "bidirectional"))
    )
    (net (code "106") (name "unconnected-(U$24-PadSD1)") (class "Default")
      (node (ref "U$24") (pin "SD1") (pinfunction "SD1_SD1") (pintype "bidirectional"))
    )
    (net (code "107") (name "unconnected-(U$24-PadSD2)") (class "Default")
      (node (ref "U$24") (pin "SD2") (pinfunction "SD2_SD2") (pintype "bidirectional"))
    )
    (net (code "108") (name "unconnected-(U$24-PadSD3)") (class "Default")
      (node (ref "U$24") (pin "SD3") (pinfunction "SD3_SD3") (pintype "bidirectional"))
    )
    (net (code "109") (name "unconnected-(U$24-PadTX)") (class "Default")
      (node (ref "U$24") (pin "TX") (pinfunction "TX_TX") (pintype "bidirectional"))
    )
    (net (code "110") (name "unconnected-(U$24-RSV-PadRSV@1)") (class "Default")
      (node (ref "U$24") (pin "RSV@1") (pinfunction "RSV_RSV@1") (pintype "bidirectional"))
    )
    (net (code "111") (name "unconnected-(U1-A4-Pad7)") (class "Default")
      (node (ref "U1") (pin "7") (pinfunction "A4_7") (pintype "bidirectional"))
    )
    (net (code "112") (name "unconnected-(U1-A5-Pad8)") (class "Default")
      (node (ref "U1") (pin "8") (pinfunction "A5_8") (pintype "bidirectional"))
    )
    (net (code "113") (name "unconnected-(U1-A6-Pad9)") (class "Default")
      (node (ref "U1") (pin "9") (pinfunction "A6_9") (pintype "bidirectional"))
    )
    (net (code "114") (name "unconnected-(U1-A7-Pad10)") (class "Default")
      (node (ref "U1") (pin "10") (pinfunction "A7_10") (pintype "bidirectional"))
    )
    (net (code "115") (name "unconnected-(U1-B4-Pad17)") (class "Default")
      (node (ref "U1") (pin "17") (pinfunction "B4_17") (pintype "bidirectional"))
    )
    (net (code "116") (name "unconnected-(U1-B5-Pad16)") (class "Default")
      (node (ref "U1") (pin "16") (pinfunction "B5_16") (pintype "bidirectional"))
    )
    (net (code "117") (name "unconnected-(U1-B6-Pad15)") (class "Default")
      (node (ref "U1") (pin "15") (pinfunction "B6_15") (pintype "bidirectional"))
    )
    (net (code "118") (name "unconnected-(U1-B7-Pad14)") (class "Default")
      (node (ref "U1") (pin "14") (pinfunction "B7_14") (pintype "bidirectional"))
    )
  )
)
